# LWOC_2_0.net
KiCad netlist of a schematic drawn in EAGLE
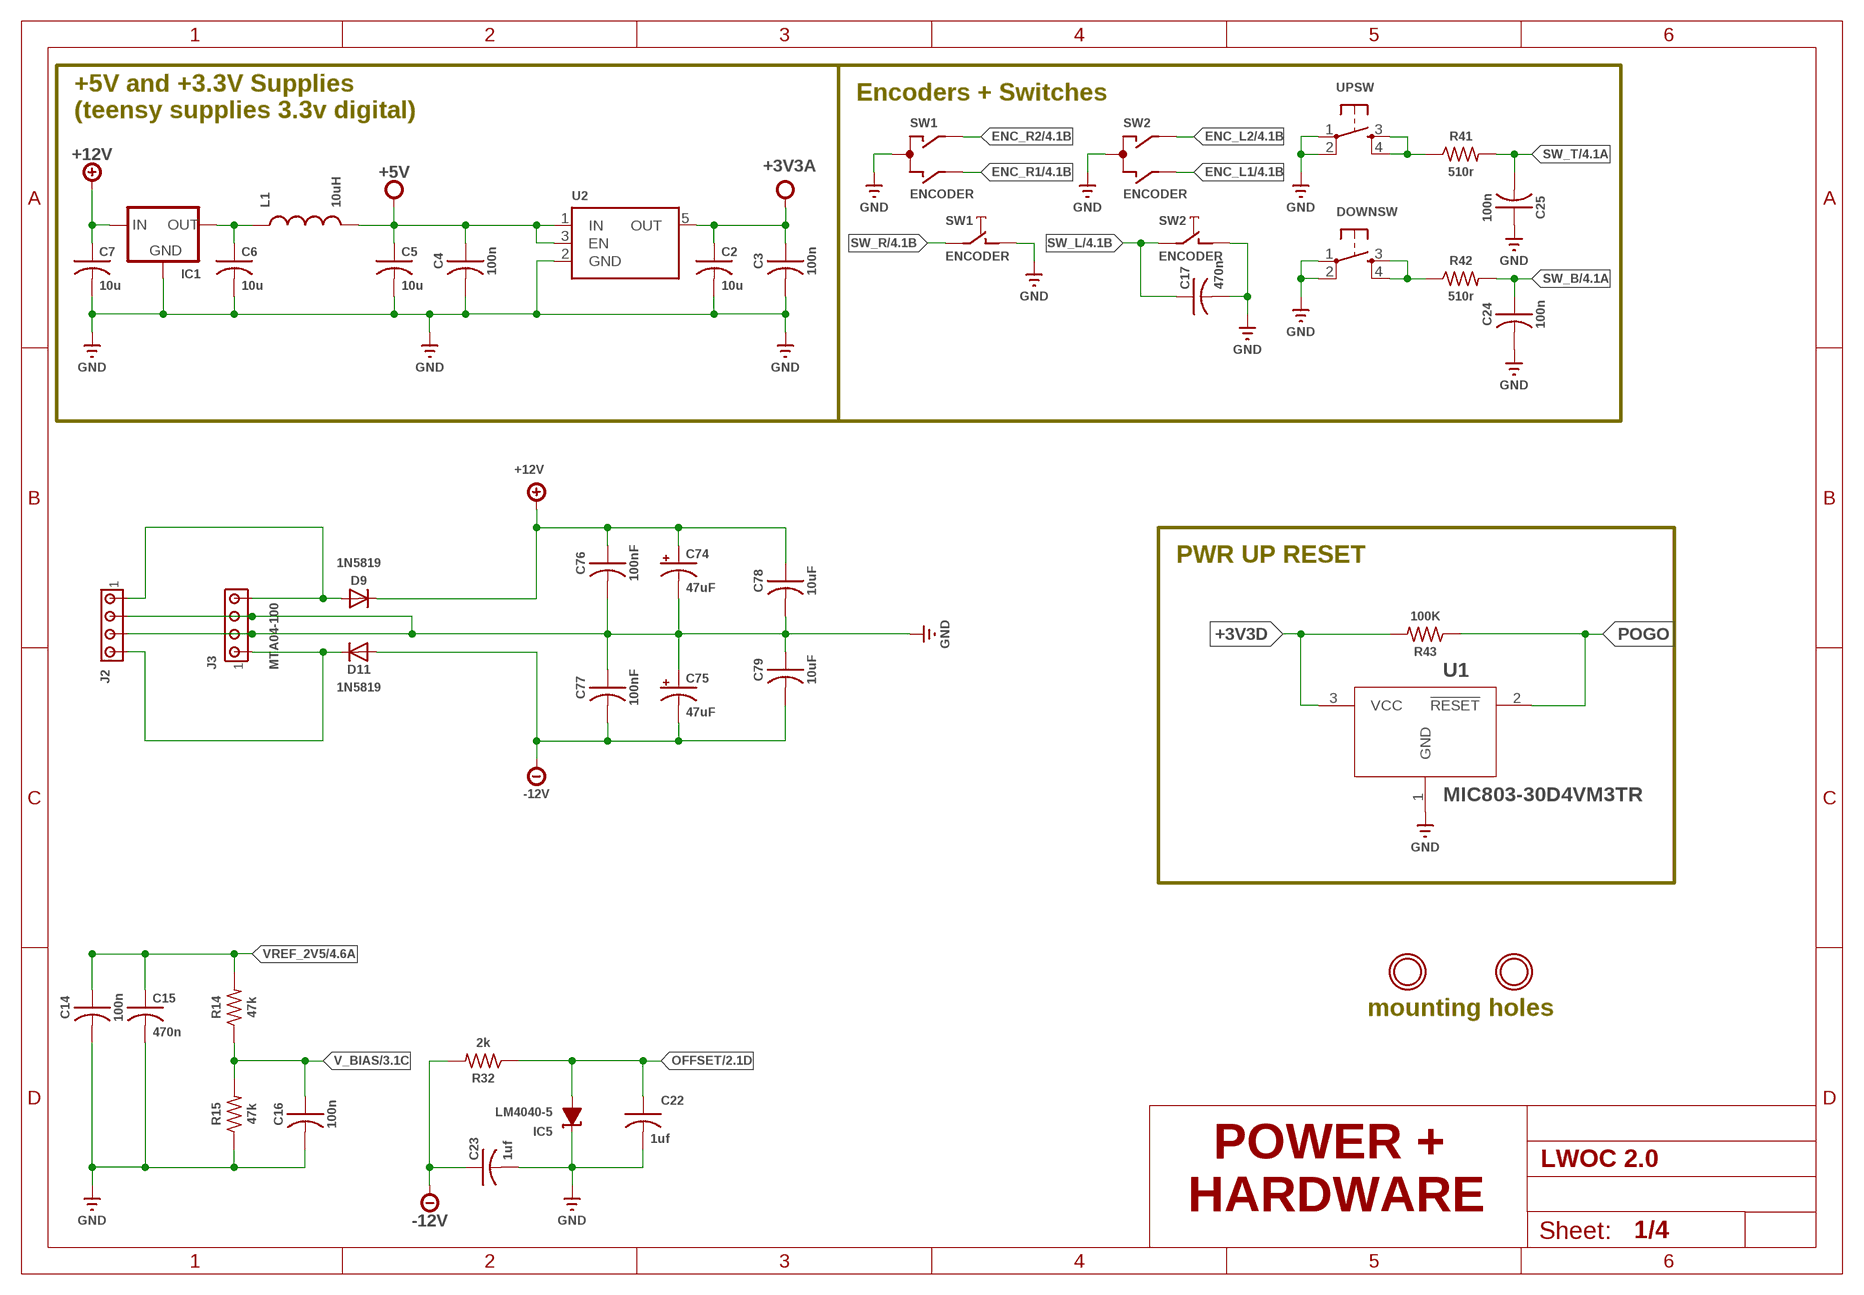
[diagram p0: schematic, sheet 1]
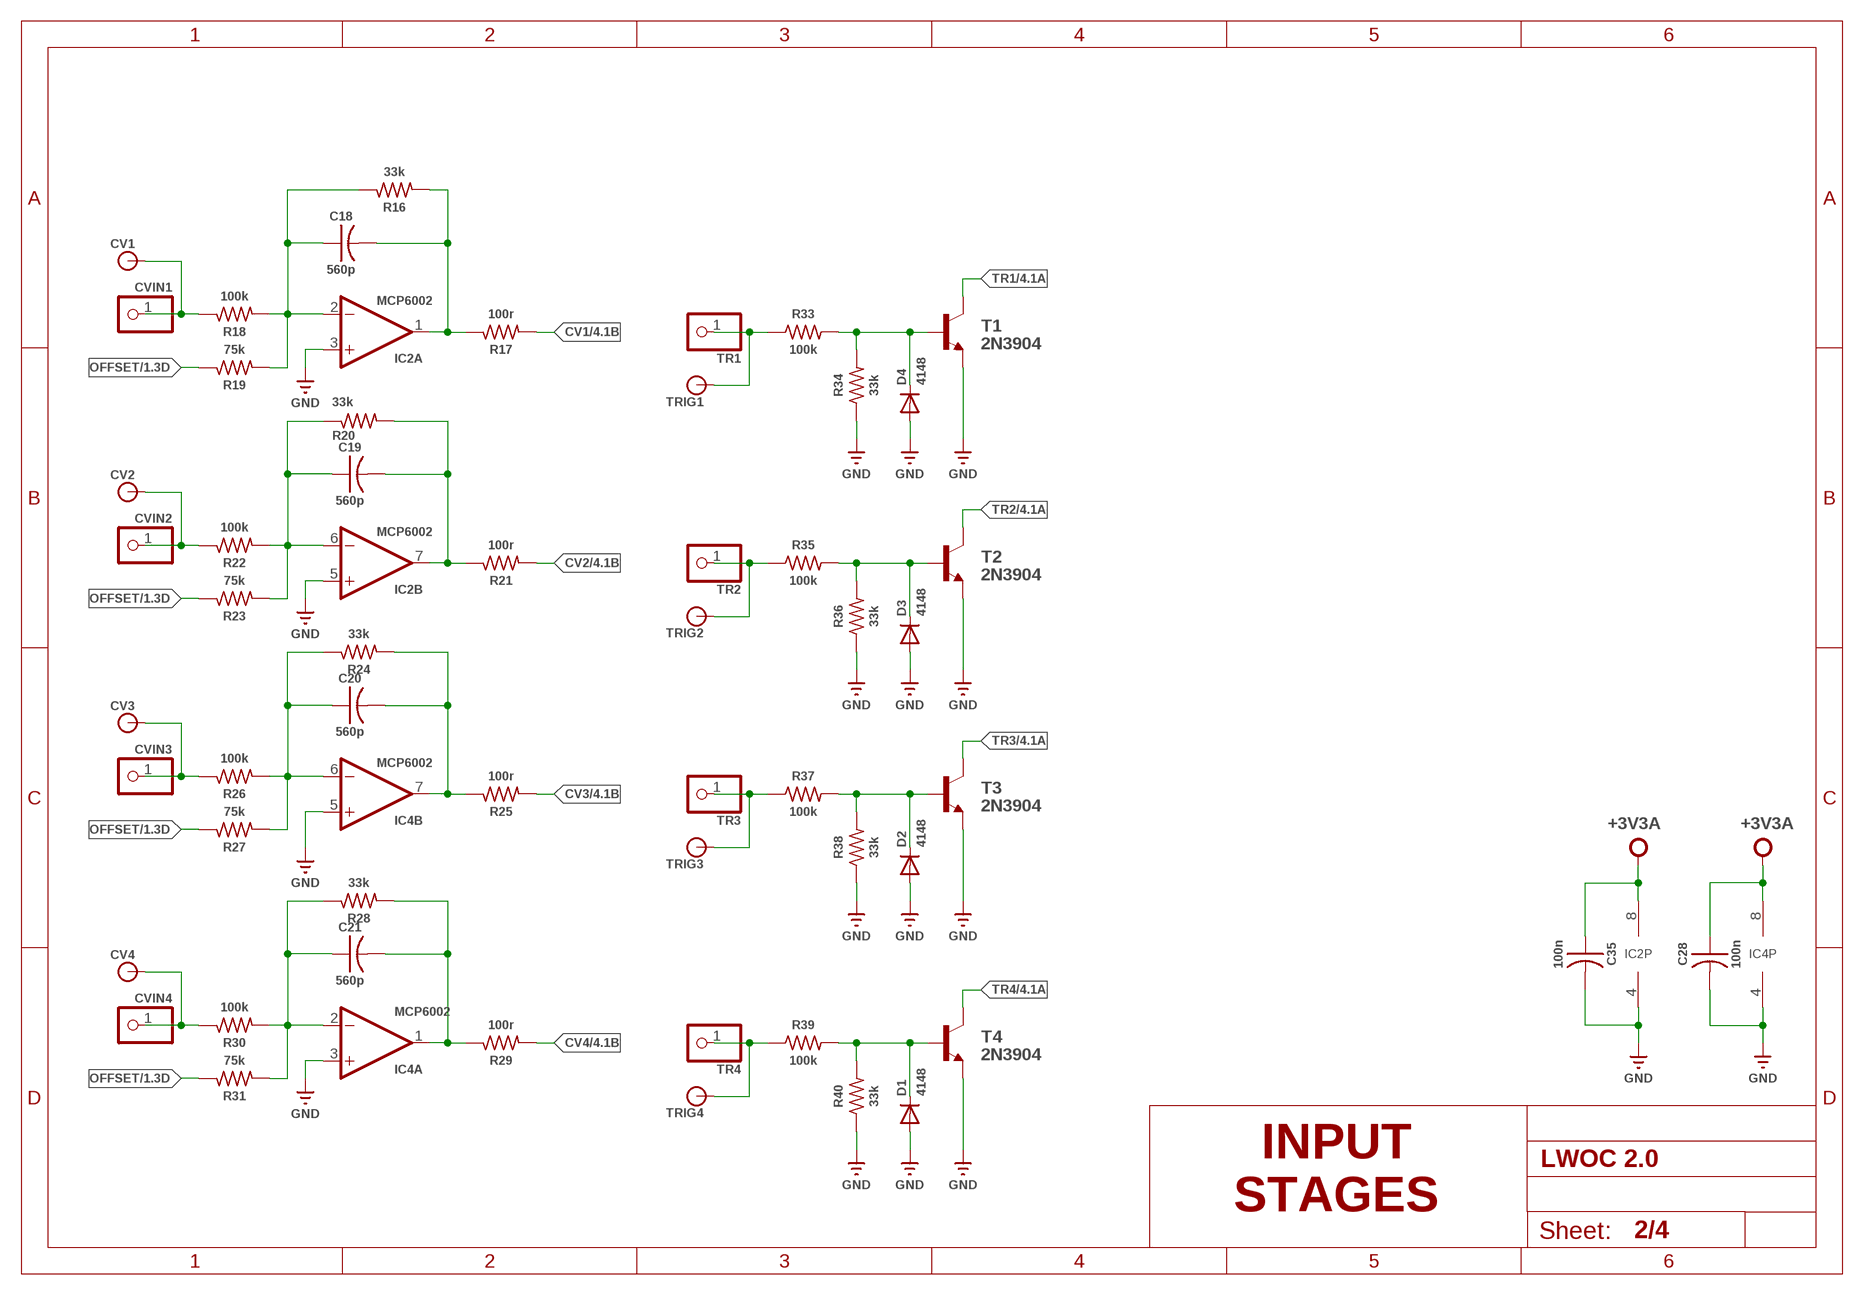
[diagram p1: schematic, sheet 2]
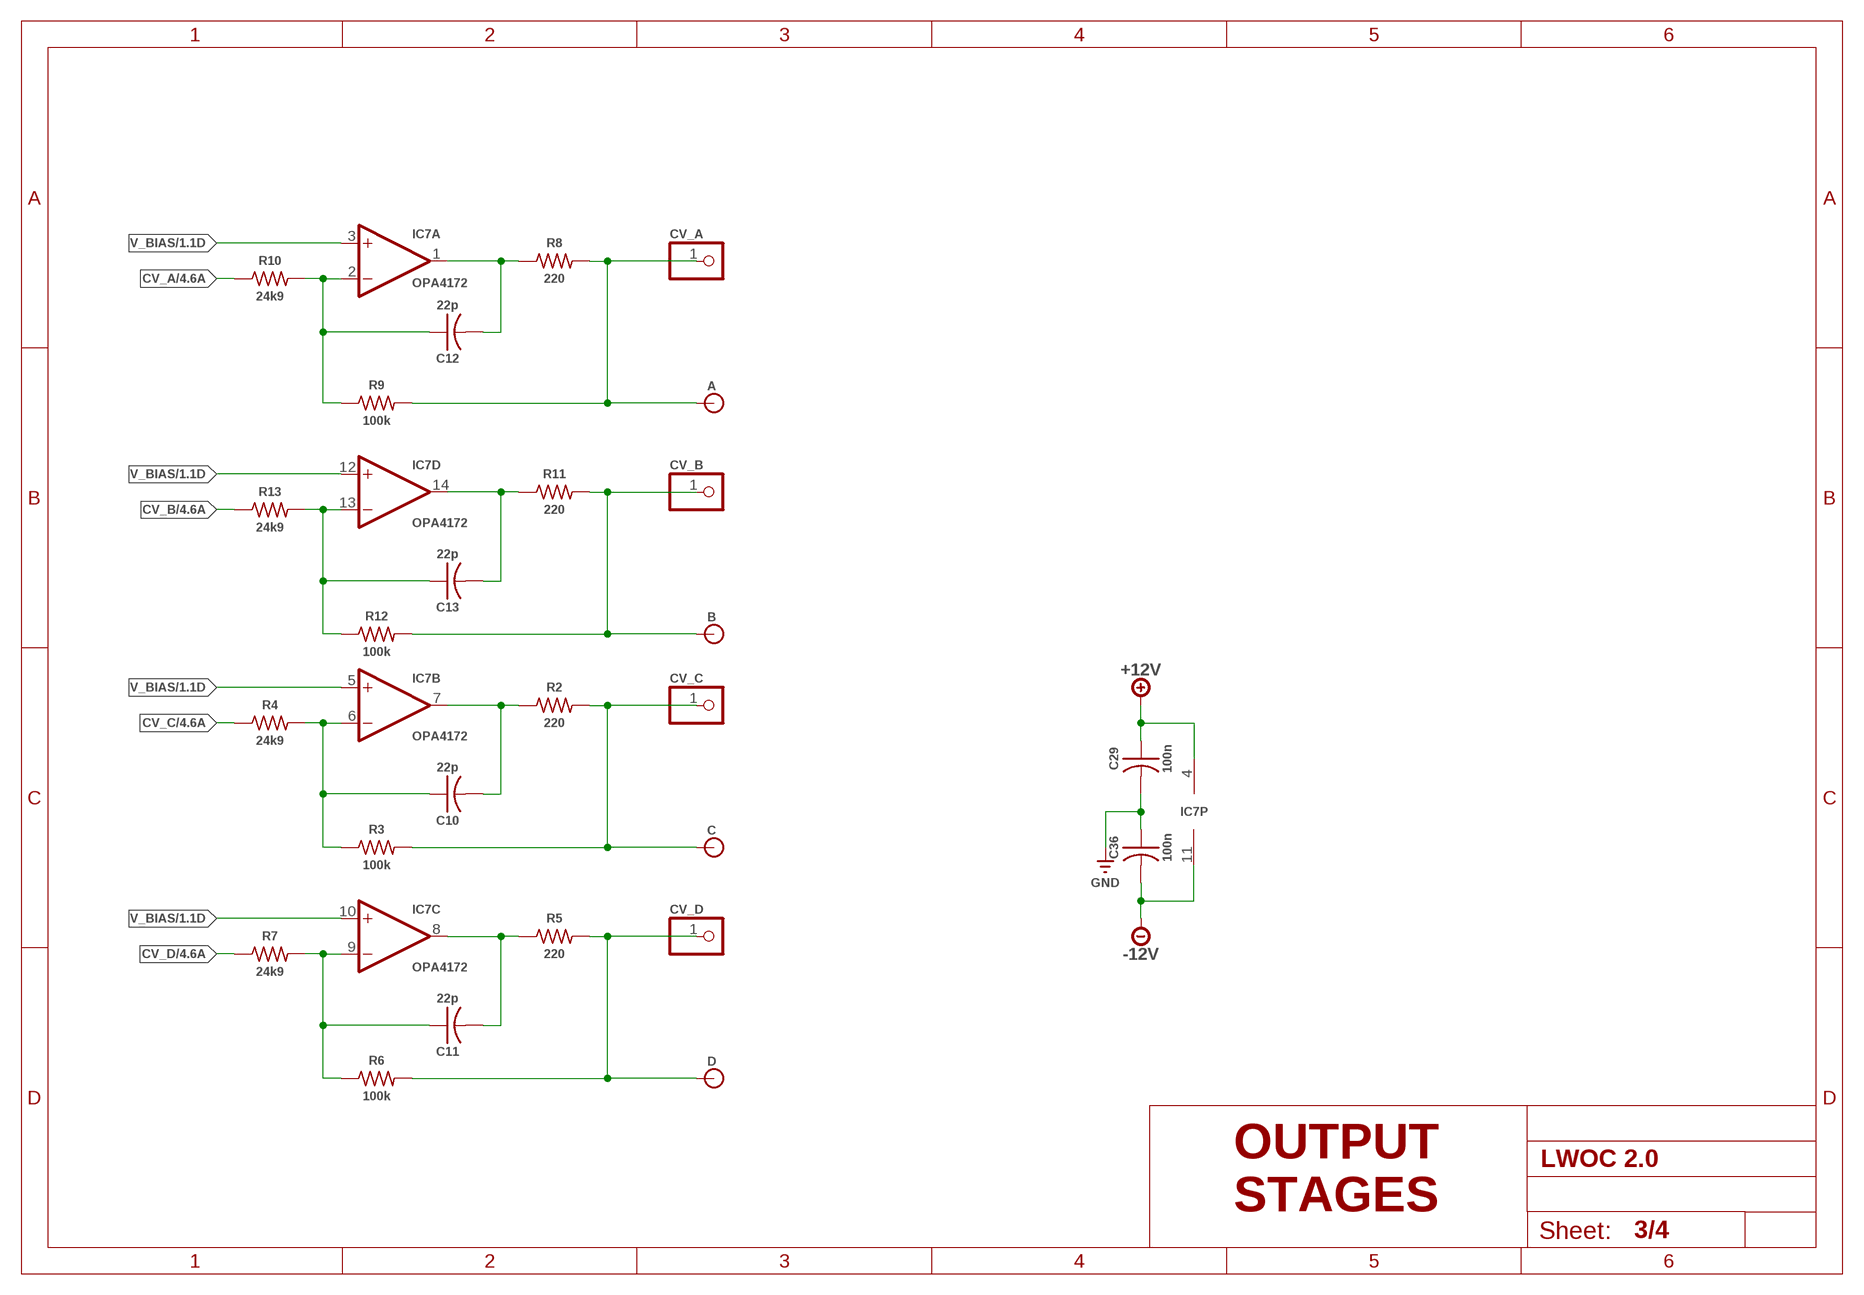
[diagram p2: schematic, sheet 3]
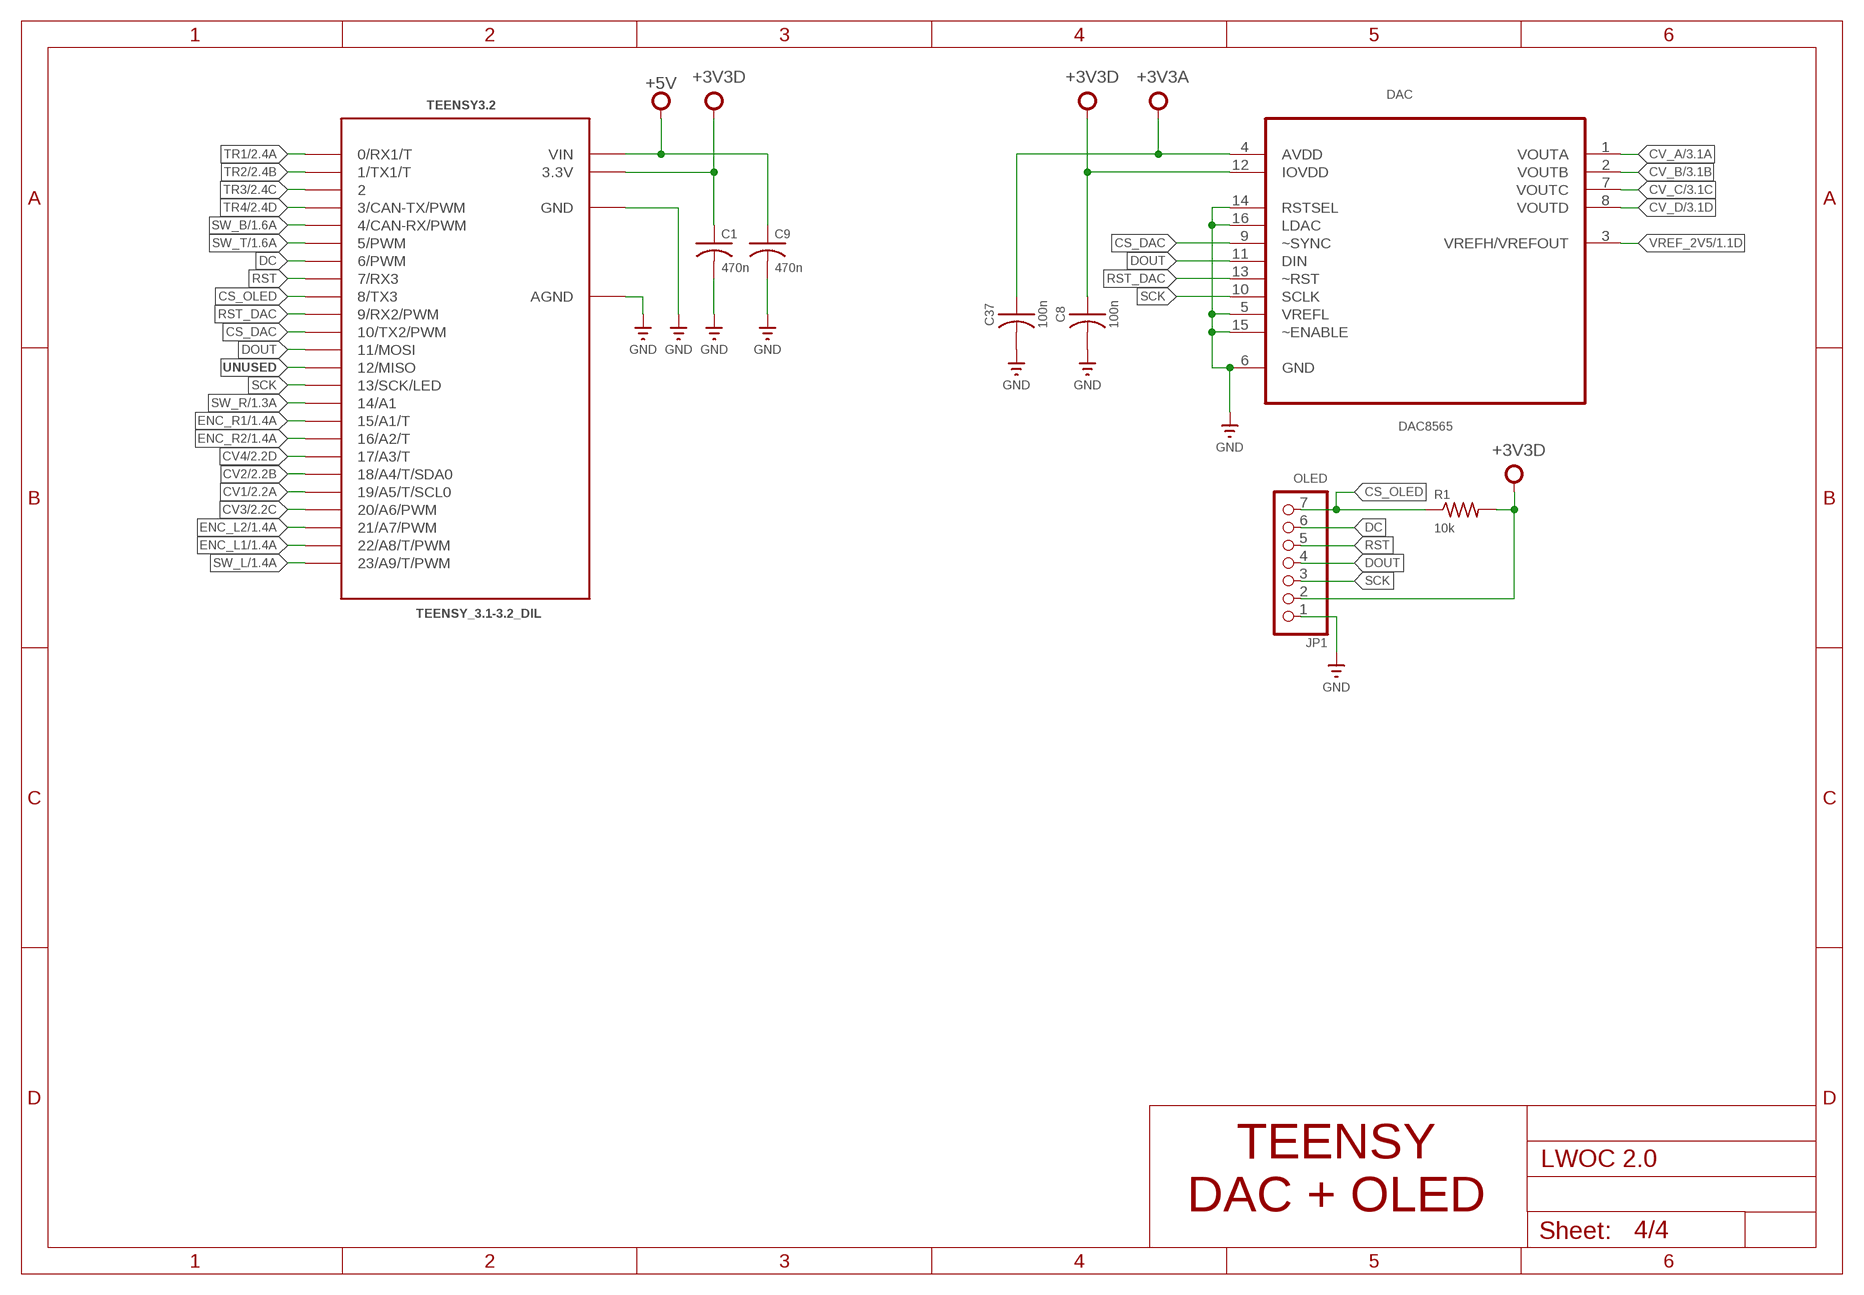
[diagram p3: schematic, sheet 4]

(export (version "E")
  (design (tool "Eeschema 10.0.6"))
  (components
    (comp (ref "C2")
      (value "10u")
      (footprint "eagle-import:C1206K")
      (libsource (lib "eagle-import") (part "C-USC1206K"))
    )
    (comp (ref "C3")
      (value "100n")
      (footprint "eagle-import:RCL_C0603K")
      (libsource (lib "eagle-import") (part "RCL_C-USC0603K"))
    )
    (comp (ref "C4")
      (value "100n")
      (footprint "eagle-import:RCL_C0603K")
      (libsource (lib "eagle-import") (part "RCL_C-USC0603K"))
    )
    (comp (ref "C5")
      (value "10u")
      (footprint "eagle-import:C1206K")
      (libsource (lib "eagle-import") (part "C-USC1206K"))
    )
    (comp (ref "C6")
      (value "10u")
      (footprint "eagle-import:C1206K")
      (libsource (lib "eagle-import") (part "C-USC1206K"))
    )
    (comp (ref "C7")
      (value "10u")
      (footprint "eagle-import:C1206K")
      (libsource (lib "eagle-import") (part "C-USC1206K"))
    )
    (comp (ref "C14")
      (value "100n")
      (footprint "eagle-import:RCL_C0603K")
      (libsource (lib "eagle-import") (part "RCL_C-USC0603K"))
    )
    (comp (ref "C15")
      (value "470n")
      (footprint "eagle-import:RCL_C0603K")
      (libsource (lib "eagle-import") (part "RCL_C-USC0603K"))
    )
    (comp (ref "C16")
      (value "100n")
      (footprint "eagle-import:RCL_C0603K")
      (libsource (lib "eagle-import") (part "RCL_C-USC0603K"))
    )
    (comp (ref "C17")
      (value "470n")
      (footprint "eagle-import:C0805K")
      (libsource (lib "eagle-import") (part "C-USC0805K"))
    )
    (comp (ref "C22")
      (value "1uf")
      (footprint "eagle-import:C0805K")
      (libsource (lib "eagle-import") (part "C-USC0805K"))
    )
    (comp (ref "C23")
      (value "1uf")
      (footprint "eagle-import:C0805K")
      (libsource (lib "eagle-import") (part "C-USC0805K"))
    )
    (comp (ref "C24")
      (value "100n")
      (footprint "eagle-import:RCL_C0603K")
      (libsource (lib "eagle-import") (part "RCL_C-USC0603K"))
    )
    (comp (ref "C25")
      (value "100n")
      (footprint "eagle-import:RCL_C0603K")
      (libsource (lib "eagle-import") (part "RCL_C-USC0603K"))
    )
    (comp (ref "C74")
      (value "47uF")
      (footprint "eagle-import:RCL_E2,5-6")
      (libsource (lib "eagle-import") (part "RCL_CPOL-USE2.5-6"))
    )
    (comp (ref "C75")
      (value "47uF")
      (footprint "eagle-import:RCL_E2,5-6")
      (libsource (lib "eagle-import") (part "RCL_CPOL-USE2.5-6"))
    )
    (comp (ref "C76")
      (value "100nF")
      (footprint "eagle-import:RCL_C0603K")
      (libsource (lib "eagle-import") (part "ripples_v40_RCL_C-USC0603K"))
    )
    (comp (ref "C77")
      (value "100nF")
      (footprint "eagle-import:RCL_C0603K")
      (libsource (lib "eagle-import") (part "ripples_v40_RCL_C-USC0603K"))
    )
    (comp (ref "C78")
      (value "10uF")
      (footprint "eagle-import:RCL_C1210")
      (libsource (lib "eagle-import") (part "RCL_C-USC1210"))
    )
    (comp (ref "C79")
      (value "10uF")
      (footprint "eagle-import:RCL_C1210")
      (libsource (lib "eagle-import") (part "RCL_C-USC1210"))
    )
    (comp (ref "D9")
      (value "1N5819")
      (footprint "eagle-import:DIODE_SOD323-W")
      (libsource (lib "eagle-import") (part "ripples_v40_DIODE_DIODE-SOD323-W"))
    )
    (comp (ref "D11")
      (value "1N5819")
      (footprint "eagle-import:DIODE_SOD323-W")
      (libsource (lib "eagle-import") (part "ripples_v40_DIODE_DIODE-SOD323-W"))
    )
    (comp (ref "DOWNSW")
      (value "SPARKFUN_TAC_SWITCHPTH")
      (footprint "eagle-import:SPARKFUN_TACTILE-PTH")
      (libsource (lib "eagle-import") (part "SPARKFUN_TAC_SWITCHPTH"))
    )
    (comp (ref "IC1")
      (value "LM1117TO252")
      (footprint "eagle-import:TO252")
      (libsource (lib "eagle-import") (part "LM1117TO252"))
    )
    (comp (ref "IC5")
      (value "LM4040-5")
      (footprint "eagle-import:DBZ_R-PDSO-G3")
      (libsource (lib "eagle-import") (part "LM4041DBZA12"))
    )
    (comp (ref "J2")
      (value "MTA04-156")
      (footprint "eagle-import:1X4MTA")
      (libsource (lib "eagle-import") (part "MTA04-156"))
    )
    (comp (ref "J3")
      (value "MTA04-100")
      (footprint "eagle-import:1X04MTA")
      (libsource (lib "eagle-import") (part "MTA04-100"))
    )
    (comp (ref "L1")
      (value "10uH")
      (footprint "eagle-import:1210")
      (libsource (lib "eagle-import") (part "INDUCTOR1210"))
    )
    (comp (ref "R14")
      (value "47k")
      (footprint "eagle-import:RCL_R0603")
      (libsource (lib "eagle-import") (part "RCL_R-US_R0603"))
    )
    (comp (ref "R15")
      (value "47k")
      (footprint "eagle-import:RCL_R0603")
      (libsource (lib "eagle-import") (part "RCL_R-US_R0603"))
    )
    (comp (ref "R32")
      (value "2k")
      (footprint "eagle-import:RCL_R0603")
      (libsource (lib "eagle-import") (part "RCL_R-US_R0603"))
    )
    (comp (ref "R41")
      (value "510r")
      (footprint "eagle-import:RCL_R0603")
      (libsource (lib "eagle-import") (part "RCL_R-US_R0603"))
    )
    (comp (ref "R42")
      (value "510r")
      (footprint "eagle-import:RCL_R0603")
      (libsource (lib "eagle-import") (part "RCL_R-US_R0603"))
    )
    (comp (ref "R43")
      (value "100K")
      (footprint "eagle-import:RCL_R0603")
      (libsource (lib "eagle-import") (part "RCL_R-US_R0603"))
    )
    (comp (ref "SW1")
      (value "ENCODER")
      (footprint "eagle-import:OG-ENCODER_ALPS_EC12E_SW")
      (libsource (lib "eagle-import") (part "OG-ENCODER_EC12E_SW"))
    )
    (comp (ref "SW2")
      (value "ENCODER")
      (footprint "eagle-import:OG-ENCODER_ALPS_EC12E_SW")
      (libsource (lib "eagle-import") (part "OG-ENCODER_EC12E_SW"))
    )
    (comp (ref "U$23")
      (value "MOUNTINGHOLE2.5")
      (footprint "eagle-import:MOUNTINGHOLE_2.5_PLATED")
      (libsource (lib "eagle-import") (part "MOUNTINGHOLE2.5"))
    )
    (comp (ref "U$26")
      (value "MOUNTINGHOLE2.5")
      (footprint "eagle-import:MOUNTINGHOLE_2.5_PLATED")
      (libsource (lib "eagle-import") (part "MOUNTINGHOLE2.5"))
    )
    (comp (ref "U1")
      (value "MIC803-30D4VM3TR")
      (footprint "eagle-import:SOT95P232X110-3N")
      (libsource (lib "eagle-import") (part "MIC803-30D4VM3TR"))
    )
    (comp (ref "U2")
      (value "ADP121")
      (footprint "eagle-import:SOT23-5")
      (libsource (lib "eagle-import") (part "ADP121"))
    )
    (comp (ref "UPSW")
      (value "SPARKFUN_TAC_SWITCHPTH")
      (footprint "eagle-import:SPARKFUN_TACTILE-PTH")
      (libsource (lib "eagle-import") (part "SPARKFUN_TAC_SWITCHPTH"))
    )
    (comp (ref "A")
      (value "BANANA_CONN")
      (footprint "eagle-import:BANANA_CONN")
      (libsource (lib "eagle-import") (part "BANANA_CONN"))
    )
    (comp (ref "B")
      (value "BANANA_CONN")
      (footprint "eagle-import:BANANA_CONN")
      (libsource (lib "eagle-import") (part "BANANA_CONN"))
    )
    (comp (ref "C")
      (value "BANANA_CONN")
      (footprint "eagle-import:BANANA_CONN")
      (libsource (lib "eagle-import") (part "BANANA_CONN"))
    )
    (comp (ref "C10")
      (value "22p")
      (footprint "eagle-import:RCL_C0603K")
      (libsource (lib "eagle-import") (part "RCL_C-USC0603K"))
    )
    (comp (ref "C11")
      (value "22p")
      (footprint "eagle-import:RCL_C0603K")
      (libsource (lib "eagle-import") (part "RCL_C-USC0603K"))
    )
    (comp (ref "C12")
      (value "22p")
      (footprint "eagle-import:RCL_C0603K")
      (libsource (lib "eagle-import") (part "RCL_C-USC0603K"))
    )
    (comp (ref "C13")
      (value "22p")
      (footprint "eagle-import:RCL_C0603K")
      (libsource (lib "eagle-import") (part "RCL_C-USC0603K"))
    )
    (comp (ref "C29")
      (value "100n")
      (footprint "eagle-import:RCL_C0603K")
      (libsource (lib "eagle-import") (part "RCL_C-USC0603K"))
    )
    (comp (ref "C36")
      (value "100n")
      (footprint "eagle-import:RCL_C0603K")
      (libsource (lib "eagle-import") (part "RCL_C-USC0603K"))
    )
    (comp (ref "CV_A")
      (value "PINHD-1X1")
      (footprint "eagle-import:1X01")
      (libsource (lib "eagle-import") (part "PINHD-1X1"))
    )
    (comp (ref "CV_B")
      (value "PINHD-1X1")
      (footprint "eagle-import:1X01")
      (libsource (lib "eagle-import") (part "PINHD-1X1"))
    )
    (comp (ref "CV_C")
      (value "PINHD-1X1")
      (footprint "eagle-import:1X01")
      (libsource (lib "eagle-import") (part "PINHD-1X1"))
    )
    (comp (ref "CV_D")
      (value "PINHD-1X1")
      (footprint "eagle-import:1X01")
      (libsource (lib "eagle-import") (part "PINHD-1X1"))
    )
    (comp (ref "D")
      (value "BANANA_CONN")
      (footprint "eagle-import:BANANA_CONN")
      (libsource (lib "eagle-import") (part "BANANA_CONN"))
    )
    (comp (ref "IC7")
      (value "OPA4172")
      (footprint "eagle-import:GM-ICS_SO14")
      (libsource (lib "eagle-import") (part "GM-ICS_TL074D"))
    )
    (comp (ref "R2")
      (value "220")
      (footprint "eagle-import:RCL_R0603")
      (libsource (lib "eagle-import") (part "RCL_R-US_R0603"))
    )
    (comp (ref "R3")
      (value "100k")
      (footprint "eagle-import:RCL_R0603")
      (libsource (lib "eagle-import") (part "RCL_R-US_R0603"))
    )
    (comp (ref "R4")
      (value "24k9")
      (footprint "eagle-import:RCL_R0603")
      (libsource (lib "eagle-import") (part "RCL_R-US_R0603"))
    )
    (comp (ref "R5")
      (value "220")
      (footprint "eagle-import:RCL_R0603")
      (libsource (lib "eagle-import") (part "RCL_R-US_R0603"))
    )
    (comp (ref "R6")
      (value "100k")
      (footprint "eagle-import:RCL_R0603")
      (libsource (lib "eagle-import") (part "RCL_R-US_R0603"))
    )
    (comp (ref "R7")
      (value "24k9")
      (footprint "eagle-import:RCL_R0603")
      (libsource (lib "eagle-import") (part "RCL_R-US_R0603"))
    )
    (comp (ref "R8")
      (value "220")
      (footprint "eagle-import:RCL_R0603")
      (libsource (lib "eagle-import") (part "RCL_R-US_R0603"))
    )
    (comp (ref "R9")
      (value "100k")
      (footprint "eagle-import:RCL_R0603")
      (libsource (lib "eagle-import") (part "RCL_R-US_R0603"))
    )
    (comp (ref "R10")
      (value "24k9")
      (footprint "eagle-import:RCL_R0603")
      (libsource (lib "eagle-import") (part "RCL_R-US_R0603"))
    )
    (comp (ref "R11")
      (value "220")
      (footprint "eagle-import:RCL_R0603")
      (libsource (lib "eagle-import") (part "RCL_R-US_R0603"))
    )
    (comp (ref "R12")
      (value "100k")
      (footprint "eagle-import:RCL_R0603")
      (libsource (lib "eagle-import") (part "RCL_R-US_R0603"))
    )
    (comp (ref "R13")
      (value "24k9")
      (footprint "eagle-import:RCL_R0603")
      (libsource (lib "eagle-import") (part "RCL_R-US_R0603"))
    )
    (comp (ref "C18")
      (value "560p")
      (footprint "eagle-import:RCL_C0603K")
      (libsource (lib "eagle-import") (part "RCL_C-USC0603K"))
    )
    (comp (ref "C19")
      (value "560p")
      (footprint "eagle-import:RCL_C0603K")
      (libsource (lib "eagle-import") (part "RCL_C-USC0603K"))
    )
    (comp (ref "C20")
      (value "560p")
      (footprint "eagle-import:RCL_C0603K")
      (libsource (lib "eagle-import") (part "RCL_C-USC0603K"))
    )
    (comp (ref "C21")
      (value "560p")
      (footprint "eagle-import:RCL_C0603K")
      (libsource (lib "eagle-import") (part "RCL_C-USC0603K"))
    )
    (comp (ref "C28")
      (value "100n")
      (footprint "eagle-import:RCL_C0603K")
      (libsource (lib "eagle-import") (part "RCL_C-USC0603K"))
    )
    (comp (ref "C35")
      (value "100n")
      (footprint "eagle-import:RCL_C0603K")
      (libsource (lib "eagle-import") (part "RCL_C-USC0603K"))
    )
    (comp (ref "CV1")
      (value "BANANA_CONN")
      (footprint "eagle-import:BANANA_CONN")
      (libsource (lib "eagle-import") (part "BANANA_CONN"))
    )
    (comp (ref "CV2")
      (value "BANANA_CONN")
      (footprint "eagle-import:BANANA_CONN")
      (libsource (lib "eagle-import") (part "BANANA_CONN"))
    )
    (comp (ref "CV3")
      (value "BANANA_CONN")
      (footprint "eagle-import:BANANA_CONN")
      (libsource (lib "eagle-import") (part "BANANA_CONN"))
    )
    (comp (ref "CV4")
      (value "BANANA_CONN")
      (footprint "eagle-import:BANANA_CONN")
      (libsource (lib "eagle-import") (part "BANANA_CONN"))
    )
    (comp (ref "CVIN1")
      (value "PINHD-1X1")
      (footprint "eagle-import:1X01")
      (libsource (lib "eagle-import") (part "PINHD-1X1"))
    )
    (comp (ref "CVIN2")
      (value "PINHD-1X1")
      (footprint "eagle-import:1X01")
      (libsource (lib "eagle-import") (part "PINHD-1X1"))
    )
    (comp (ref "CVIN3")
      (value "PINHD-1X1")
      (footprint "eagle-import:1X01")
      (libsource (lib "eagle-import") (part "PINHD-1X1"))
    )
    (comp (ref "CVIN4")
      (value "PINHD-1X1")
      (footprint "eagle-import:1X01")
      (libsource (lib "eagle-import") (part "PINHD-1X1"))
    )
    (comp (ref "D1")
      (value "4148")
      (footprint "eagle-import:DIODE_SOD323-W")
      (libsource (lib "eagle-import") (part "DIODE_DIODE-SOD323-W"))
    )
    (comp (ref "D2")
      (value "4148")
      (footprint "eagle-import:DIODE_SOD323-W")
      (libsource (lib "eagle-import") (part "DIODE_DIODE-SOD323-W"))
    )
    (comp (ref "D3")
      (value "4148")
      (footprint "eagle-import:DIODE_SOD323-W")
      (libsource (lib "eagle-import") (part "DIODE_DIODE-SOD323-W"))
    )
    (comp (ref "D4")
      (value "4148")
      (footprint "eagle-import:DIODE_SOD323-W")
      (libsource (lib "eagle-import") (part "DIODE_DIODE-SOD323-W"))
    )
    (comp (ref "IC2")
      (value "MCP6002")
      (footprint "eagle-import:GM-ICS_SO08")
      (libsource (lib "eagle-import") (part "GM-ICS_TL072D"))
    )
    (comp (ref "IC4")
      (value "MCP6002")
      (footprint "eagle-import:GM-ICS_SO08")
      (libsource (lib "eagle-import") (part "GM-ICS_TL072D"))
    )
    (comp (ref "R16")
      (value "33k")
      (footprint "eagle-import:RCL_R0603")
      (libsource (lib "eagle-import") (part "RCL_R-US_R0603"))
    )
    (comp (ref "R17")
      (value "100r")
      (footprint "eagle-import:RCL_R0603")
      (libsource (lib "eagle-import") (part "RCL_R-US_R0603"))
    )
    (comp (ref "R18")
      (value "100k")
      (footprint "eagle-import:RCL_R0603")
      (libsource (lib "eagle-import") (part "RCL_R-US_R0603"))
    )
    (comp (ref "R19")
      (value "75k")
      (footprint "eagle-import:RCL_R0603")
      (libsource (lib "eagle-import") (part "RCL_R-US_R0603"))
    )
    (comp (ref "R20")
      (value "33k")
      (footprint "eagle-import:RCL_R0603")
      (libsource (lib "eagle-import") (part "RCL_R-US_R0603"))
    )
    (comp (ref "R21")
      (value "100r")
      (footprint "eagle-import:RCL_R0603")
      (libsource (lib "eagle-import") (part "RCL_R-US_R0603"))
    )
    (comp (ref "R22")
      (value "100k")
      (footprint "eagle-import:RCL_R0603")
      (libsource (lib "eagle-import") (part "RCL_R-US_R0603"))
    )
    (comp (ref "R23")
      (value "75k")
      (footprint "eagle-import:RCL_R0603")
      (libsource (lib "eagle-import") (part "RCL_R-US_R0603"))
    )
    (comp (ref "R24")
      (value "33k")
      (footprint "eagle-import:RCL_R0603")
      (libsource (lib "eagle-import") (part "RCL_R-US_R0603"))
    )
    (comp (ref "R25")
      (value "100r")
      (footprint "eagle-import:RCL_R0603")
      (libsource (lib "eagle-import") (part "RCL_R-US_R0603"))
    )
    (comp (ref "R26")
      (value "100k")
      (footprint "eagle-import:RCL_R0603")
      (libsource (lib "eagle-import") (part "RCL_R-US_R0603"))
    )
    (comp (ref "R27")
      (value "75k")
      (footprint "eagle-import:RCL_R0603")
      (libsource (lib "eagle-import") (part "RCL_R-US_R0603"))
    )
    (comp (ref "R28")
      (value "33k")
      (footprint "eagle-import:RCL_R0603")
      (libsource (lib "eagle-import") (part "RCL_R-US_R0603"))
    )
    (comp (ref "R29")
      (value "100r")
      (footprint "eagle-import:RCL_R0603")
      (libsource (lib "eagle-import") (part "RCL_R-US_R0603"))
    )
    (comp (ref "R30")
      (value "100k")
      (footprint "eagle-import:RCL_R0603")
      (libsource (lib "eagle-import") (part "RCL_R-US_R0603"))
    )
    (comp (ref "R31")
      (value "75k")
      (footprint "eagle-import:RCL_R0603")
      (libsource (lib "eagle-import") (part "RCL_R-US_R0603"))
    )
    (comp (ref "R33")
      (value "100k")
      (footprint "eagle-import:RCL_R0603")
      (libsource (lib "eagle-import") (part "RCL_R-US_R0603"))
    )
    (comp (ref "R34")
      (value "33k")
      (footprint "eagle-import:RCL_R0603")
      (libsource (lib "eagle-import") (part "RCL_R-US_R0603"))
    )
    (comp (ref "R35")
      (value "100k")
      (footprint "eagle-import:RCL_R0603")
      (libsource (lib "eagle-import") (part "RCL_R-US_R0603"))
    )
    (comp (ref "R36")
      (value "33k")
      (footprint "eagle-import:RCL_R0603")
      (libsource (lib "eagle-import") (part "RCL_R-US_R0603"))
    )
    (comp (ref "R37")
      (value "100k")
      (footprint "eagle-import:RCL_R0603")
      (libsource (lib "eagle-import") (part "RCL_R-US_R0603"))
    )
    (comp (ref "R38")
      (value "33k")
      (footprint "eagle-import:RCL_R0603")
      (libsource (lib "eagle-import") (part "RCL_R-US_R0603"))
    )
    (comp (ref "R39")
      (value "100k")
      (footprint "eagle-import:RCL_R0603")
      (libsource (lib "eagle-import") (part "RCL_R-US_R0603"))
    )
    (comp (ref "R40")
      (value "33k")
      (footprint "eagle-import:RCL_R0603")
      (libsource (lib "eagle-import") (part "RCL_R-US_R0603"))
    )
    (comp (ref "T1")
      (value "2N3904")
      (footprint "eagle-import:SOT23-BEC")
      (libsource (lib "eagle-import") (part "-NPN-SOT23-BECMMBT3904LT1"))
    )
    (comp (ref "T2")
      (value "2N3904")
      (footprint "eagle-import:SOT23-BEC")
      (libsource (lib "eagle-import") (part "-NPN-SOT23-BECMMBT3904LT1"))
    )
    (comp (ref "T3")
      (value "2N3904")
      (footprint "eagle-import:SOT23-BEC")
      (libsource (lib "eagle-import") (part "-NPN-SOT23-BECMMBT3904LT1"))
    )
    (comp (ref "T4")
      (value "2N3904")
      (footprint "eagle-import:SOT23-BEC")
      (libsource (lib "eagle-import") (part "-NPN-SOT23-BECMMBT3904LT1"))
    )
    (comp (ref "TR1")
      (value "PINHD-1X1")
      (footprint "eagle-import:1X01")
      (libsource (lib "eagle-import") (part "PINHD-1X1"))
    )
    (comp (ref "TR2")
      (value "PINHD-1X1")
      (footprint "eagle-import:1X01")
      (libsource (lib "eagle-import") (part "PINHD-1X1"))
    )
    (comp (ref "TR3")
      (value "PINHD-1X1")
      (footprint "eagle-import:1X01")
      (libsource (lib "eagle-import") (part "PINHD-1X1"))
    )
    (comp (ref "TR4")
      (value "PINHD-1X1")
      (footprint "eagle-import:1X01")
      (libsource (lib "eagle-import") (part "PINHD-1X1"))
    )
    (comp (ref "TRIG1")
      (value "BANANA_CONN")
      (footprint "eagle-import:BANANA_CONN")
      (libsource (lib "eagle-import") (part "BANANA_CONN"))
    )
    (comp (ref "TRIG2")
      (value "BANANA_CONN")
      (footprint "eagle-import:BANANA_CONN")
      (libsource (lib "eagle-import") (part "BANANA_CONN"))
    )
    (comp (ref "TRIG3")
      (value "BANANA_CONN")
      (footprint "eagle-import:BANANA_CONN")
      (libsource (lib "eagle-import") (part "BANANA_CONN"))
    )
    (comp (ref "TRIG4")
      (value "BANANA_CONN")
      (footprint "eagle-import:BANANA_CONN")
      (libsource (lib "eagle-import") (part "BANANA_CONN"))
    )
    (comp (ref "C1")
      (value "470n")
      (footprint "eagle-import:C0805K")
      (libsource (lib "eagle-import") (part "C-USC0805K"))
    )
    (comp (ref "C8")
      (value "100n")
      (footprint "eagle-import:RCL_C0603K")
      (libsource (lib "eagle-import") (part "RCL_C-USC0603K"))
    )
    (comp (ref "C9")
      (value "470n")
      (footprint "eagle-import:C0805K")
      (libsource (lib "eagle-import") (part "C-USC0805K"))
    )
    (comp (ref "C37")
      (value "100n")
      (footprint "eagle-import:RCL_C0603K")
      (libsource (lib "eagle-import") (part "RCL_C-USC0603K"))
    )
    (comp (ref "DAC")
      (value "DAC8565")
      (footprint "eagle-import:SOP65P640X120-16N")
      (fields (field (name "MF") "Texas Instruments") (field (name "MP") "DAC8565IAPW"))
      (libsource (lib "eagle-import") (part "DAC8565IAPW"))
    )
    (comp (ref "JP1")
      (value "OLED")
      (footprint "eagle-import:1X07")
      (libsource (lib "eagle-import") (part "PINHD-1X7"))
    )
    (comp (ref "R1")
      (value "10k")
      (footprint "eagle-import:M0805")
      (libsource (lib "eagle-import") (part "R-US_M0805"))
    )
    (comp (ref "TEENSY3.2")
      (value "TEENSY_3.1-3.2_DIL")
      (footprint "eagle-import:TEENSY_3.0-3.2&LC_DIL")
      (libsource (lib "eagle-import") (part "TEENSY_3.1-3.2_DIL"))
    )
  )
  (nets
    (net (code "1") (name "+3V3A") (class "Default")
      (node (ref "C2") (pin "1") (pinfunction "1_1") (pintype "passive"))
      (node (ref "C28") (pin "1") (pinfunction "1_1") (pintype "passive"))
      (node (ref "C3") (pin "1") (pinfunction "1_1") (pintype "passive"))
      (node (ref "C35") (pin "1") (pinfunction "1_1") (pintype "passive"))
      (node (ref "C37") (pin "1") (pinfunction "1_1") (pintype "passive"))
      (node (ref "DAC") (pin "4") (pinfunction "AVDD_4") (pintype "power_in"))
      (node (ref "IC2") (pin "8") (pinfunction "V+_8") (pintype "power_in"))
      (node (ref "IC4") (pin "8") (pinfunction "V+_8") (pintype "power_in"))
      (node (ref "U2") (pin "5") (pinfunction "OUT_5") (pintype "bidirectional"))
    )
    (net (code "2") (name "+3V3D") (class "Default")
      (node (ref "C1") (pin "1") (pinfunction "1_1") (pintype "passive"))
      (node (ref "C8") (pin "1") (pinfunction "1_1") (pintype "passive"))
      (node (ref "DAC") (pin "12") (pinfunction "IOVDD_12") (pintype "power_in"))
      (node (ref "JP1") (pin "2") (pinfunction "2_2") (pintype "passive"))
      (node (ref "R1") (pin "2") (pinfunction "2_2") (pintype "passive"))
      (node (ref "R43") (pin "2") (pinfunction "2_2") (pintype "passive"))
      (node (ref "TEENSY3.2") (pin "3.3V") (pinfunction "3.3V_3.3V") (pintype "power_in"))
      (node (ref "U1") (pin "3") (pinfunction "VCC_3") (pintype "power_in"))
    )
    (net (code "3") (name "+5V") (class "Default")
      (node (ref "C4") (pin "1") (pinfunction "1_1") (pintype "passive"))
      (node (ref "C5") (pin "1") (pinfunction "1_1") (pintype "passive"))
      (node (ref "C9") (pin "1") (pinfunction "1_1") (pintype "passive"))
      (node (ref "L1") (pin "2") (pinfunction "2_2") (pintype "passive"))
      (node (ref "TEENSY3.2") (pin "VIN") (pinfunction "VIN_VIN") (pintype "power_in"))
      (node (ref "U2") (pin "1") (pinfunction "IN_1") (pintype "bidirectional"))
      (node (ref "U2") (pin "3") (pinfunction "EN_3") (pintype "bidirectional"))
    )
    (net (code "4") (name "+12V") (class "Default")
      (node (ref "C29") (pin "1") (pinfunction "1_1") (pintype "passive"))
      (node (ref "C7") (pin "1") (pinfunction "1_1") (pintype "passive"))
      (node (ref "C74") (pin "+") (pinfunction "+_+") (pintype "passive"))
      (node (ref "C76") (pin "1") (pinfunction "1_1") (pintype "passive"))
      (node (ref "C78") (pin "1") (pinfunction "1_1") (pintype "passive"))
      (node (ref "D9") (pin "C") (pinfunction "C_C") (pintype "passive"))
      (node (ref "IC1") (pin "2") (pinfunction "IN_2") (pintype "input"))
      (node (ref "IC7") (pin "4") (pinfunction "V+_4") (pintype "power_in"))
    )
    (net (code "5") (name "-12V") (class "Default")
      (node (ref "C23") (pin "1") (pinfunction "1_1") (pintype "passive"))
      (node (ref "C36") (pin "2") (pinfunction "2_2") (pintype "passive"))
      (node (ref "C75") (pin "-") (pinfunction "-_-") (pintype "passive"))
      (node (ref "C77") (pin "2") (pinfunction "2_2") (pintype "passive"))
      (node (ref "C79") (pin "2") (pinfunction "2_2") (pintype "passive"))
      (node (ref "D11") (pin "A") (pinfunction "A_A") (pintype "passive"))
      (node (ref "IC7") (pin "11") (pinfunction "V-_11") (pintype "power_in"))
      (node (ref "R32") (pin "2") (pinfunction "2_2") (pintype "passive"))
    )
    (net (code "6") (name "CS_DAC") (class "Default")
      (node (ref "DAC") (pin "9") (pinfunction "~{SYNC}_9") (pintype "input"))
      (node (ref "TEENSY3.2") (pin "10") (pinfunction "10/TX2/PWM_10") (pintype "bidirectional"))
    )
    (net (code "7") (name "CS_OLED") (class "Default")
      (node (ref "JP1") (pin "7") (pinfunction "7_7") (pintype "passive"))
      (node (ref "R1") (pin "1") (pinfunction "1_1") (pintype "passive"))
      (node (ref "TEENSY3.2") (pin "8") (pinfunction "8/TX3_8") (pintype "bidirectional"))
    )
    (net (code "8") (name "CV1") (class "Default")
      (node (ref "R17") (pin "2") (pinfunction "2_2") (pintype "passive"))
      (node (ref "TEENSY3.2") (pin "19/A5") (pinfunction "19/A5/T/SCL0_19/A5") (pintype "bidirectional"))
    )
    (net (code "9") (name "CV2") (class "Default")
      (node (ref "R21") (pin "2") (pinfunction "2_2") (pintype "passive"))
      (node (ref "TEENSY3.2") (pin "18/A4") (pinfunction "18/A4/T/SDA0_18/A4") (pintype "bidirectional"))
    )
    (net (code "10") (name "CV3") (class "Default")
      (node (ref "R25") (pin "2") (pinfunction "2_2") (pintype "passive"))
      (node (ref "TEENSY3.2") (pin "20/A6") (pinfunction "20/A6/PWM_20/A6") (pintype "bidirectional"))
    )
    (net (code "11") (name "CV4") (class "Default")
      (node (ref "R29") (pin "2") (pinfunction "2_2") (pintype "passive"))
      (node (ref "TEENSY3.2") (pin "17/A3") (pinfunction "17/A3/T_17/A3") (pintype "bidirectional"))
    )
    (net (code "12") (name "CV_A") (class "Default")
      (node (ref "DAC") (pin "1") (pinfunction "VOUTA_1") (pintype "output"))
      (node (ref "R10") (pin "1") (pinfunction "1_1") (pintype "passive"))
    )
    (net (code "13") (name "CV_B") (class "Default")
      (node (ref "DAC") (pin "2") (pinfunction "VOUTB_2") (pintype "output"))
      (node (ref "R13") (pin "1") (pinfunction "1_1") (pintype "passive"))
    )
    (net (code "14") (name "CV_C") (class "Default")
      (node (ref "DAC") (pin "7") (pinfunction "VOUTC_7") (pintype "output"))
      (node (ref "R4") (pin "1") (pinfunction "1_1") (pintype "passive"))
    )
    (net (code "15") (name "CV_D") (class "Default")
      (node (ref "DAC") (pin "8") (pinfunction "VOUTD_8") (pintype "output"))
      (node (ref "R7") (pin "1") (pinfunction "1_1") (pintype "passive"))
    )
    (net (code "16") (name "DC") (class "Default")
      (node (ref "JP1") (pin "6") (pinfunction "6_6") (pintype "passive"))
      (node (ref "TEENSY3.2") (pin "6") (pinfunction "6/PWM_6") (pintype "bidirectional"))
    )
    (net (code "17") (name "DOUT") (class "Default")
      (node (ref "DAC") (pin "11") (pinfunction "DIN_11") (pintype "input"))
      (node (ref "JP1") (pin "4") (pinfunction "4_4") (pintype "passive"))
      (node (ref "TEENSY3.2") (pin "11") (pinfunction "11/MOSI_11") (pintype "bidirectional"))
    )
    (net (code "18") (name "ENC_L1") (class "Default")
      (node (ref "SW2") (pin "B") (pinfunction "B_B") (pintype "passive"))
      (node (ref "TEENSY3.2") (pin "22/A8") (pinfunction "22/A8/T/PWM_22/A8") (pintype "bidirectional"))
    )
    (net (code "19") (name "ENC_L2") (class "Default")
      (node (ref "SW2") (pin "A") (pinfunction "A_A") (pintype "passive"))
      (node (ref "TEENSY3.2") (pin "21/A7") (pinfunction "21/A7/PWM_21/A7") (pintype "bidirectional"))
    )
    (net (code "20") (name "ENC_R1") (class "Default")
      (node (ref "SW1") (pin "B") (pinfunction "B_B") (pintype "passive"))
      (node (ref "TEENSY3.2") (pin "15/A1") (pinfunction "15/A1/T_15/A1") (pintype "bidirectional"))
    )
    (net (code "21") (name "ENC_R2") (class "Default")
      (node (ref "SW1") (pin "A") (pinfunction "A_A") (pintype "passive"))
      (node (ref "TEENSY3.2") (pin "16/A2") (pinfunction "16/A2/T_16/A2") (pintype "bidirectional"))
    )
    (net (code "22") (name "GND") (class "Default")
      (node (ref "C1") (pin "2") (pinfunction "2_2") (pintype "passive"))
      (node (ref "C14") (pin "2") (pinfunction "2_2") (pintype "passive"))
      (node (ref "C15") (pin "2") (pinfunction "2_2") (pintype "passive"))
      (node (ref "C16") (pin "2") (pinfunction "2_2") (pintype "passive"))
      (node (ref "C17") (pin "2") (pinfunction "2_2") (pintype "passive"))
      (node (ref "C2") (pin "2") (pinfunction "2_2") (pintype "passive"))
      (node (ref "C22") (pin "2") (pinfunction "2_2") (pintype "passive"))
      (node (ref "C23") (pin "2") (pinfunction "2_2") (pintype "passive"))
      (node (ref "C24") (pin "2") (pinfunction "2_2") (pintype "passive"))
      (node (ref "C25") (pin "1") (pinfunction "1_1") (pintype "passive"))
      (node (ref "C28") (pin "2") (pinfunction "2_2") (pintype "passive"))
      (node (ref "C29") (pin "2") (pinfunction "2_2") (pintype "passive"))
      (node (ref "C3") (pin "2") (pinfunction "2_2") (pintype "passive"))
      (node (ref "C35") (pin "2") (pinfunction "2_2") (pintype "passive"))
      (node (ref "C36") (pin "1") (pinfunction "1_1") (pintype "passive"))
      (node (ref "C37") (pin "2") (pinfunction "2_2") (pintype "passive"))
      (node (ref "C4") (pin "2") (pinfunction "2_2") (pintype "passive"))
      (node (ref "C5") (pin "2") (pinfunction "2_2") (pintype "passive"))
      (node (ref "C6") (pin "2") (pinfunction "2_2") (pintype "passive"))
      (node (ref "C7") (pin "2") (pinfunction "2_2") (pintype "passive"))
      (node (ref "C74") (pin "-") (pinfunction "-_-") (pintype "passive"))
      (node (ref "C75") (pin "+") (pinfunction "+_+") (pintype "passive"))
      (node (ref "C76") (pin "2") (pinfunction "2_2") (pintype "passive"))
      (node (ref "C77") (pin "1") (pinfunction "1_1") (pintype "passive"))
      (node (ref "C78") (pin "2") (pinfunction "2_2") (pintype "passive"))
      (node (ref "C79") (pin "1") (pinfunction "1_1") (pintype "passive"))
      (node (ref "C8") (pin "2") (pinfunction "2_2") (pintype "passive"))
      (node (ref "C9") (pin "2") (pinfunction "2_2") (pintype "passive"))
      (node (ref "D1") (pin "A") (pinfunction "A_A") (pintype "passive"))
      (node (ref "D2") (pin "A") (pinfunction "A_A") (pintype "passive"))
      (node (ref "D3") (pin "A") (pinfunction "A_A") (pintype "passive"))
      (node (ref "D4") (pin "A") (pinfunction "A_A") (pintype "passive"))
      (node (ref "DAC") (pin "14") (pinfunction "RSTSEL_14") (pintype "input"))
      (node (ref "DAC") (pin "15") (pinfunction "~{ENABLE}_15") (pintype "input"))
      (node (ref "DAC") (pin "16") (pinfunction "LDAC_16") (pintype "input"))
      (node (ref "DAC") (pin "5") (pinfunction "VREFL_5") (pintype "input"))
      (node (ref "DAC") (pin "6") (pinfunction "GND_6") (pintype "passive"))
      (node (ref "DOWNSW") (pin "1") (pinfunction "1_1") (pintype "passive"))
      (node (ref "DOWNSW") (pin "2") (pinfunction "2_2") (pintype "passive"))
      (node (ref "IC1") (pin "1") (pinfunction "GND_1") (pintype "input"))
      (node (ref "IC2") (pin "3") (pinfunction "+IN_3") (pintype "input"))
      (node (ref "IC2") (pin "4") (pinfunction "V-_4") (pintype "power_in"))
      (node (ref "IC2") (pin "5") (pinfunction "+IN_5") (pintype "input"))
      (node (ref "IC4") (pin "3") (pinfunction "+IN_3") (pintype "input"))
      (node (ref "IC4") (pin "4") (pinfunction "V-_4") (pintype "power_in"))
      (node (ref "IC4") (pin "5") (pinfunction "+IN_5") (pintype "input"))
      (node (ref "IC5") (pin "1") (pinfunction "C_1") (pintype "passive"))
      (node (ref "J2") (pin "2") (pinfunction "2_2") (pintype "passive"))
      (node (ref "J2") (pin "3") (pinfunction "3_3") (pintype "passive"))
      (node (ref "J3") (pin "2") (pinfunction "3_2") (pintype "bidirectional"))
      (node (ref "J3") (pin "3") (pinfunction "2_3") (pintype "bidirectional"))
      (node (ref "JP1") (pin "1") (pinfunction "1_1") (pintype "passive"))
      (node (ref "R15") (pin "1") (pinfunction "1_1") (pintype "passive"))
      (node (ref "R34") (pin "1") (pinfunction "1_1") (pintype "passive"))
      (node (ref "R36") (pin "1") (pinfunction "1_1") (pintype "passive"))
      (node (ref "R38") (pin "1") (pinfunction "1_1") (pintype "passive"))
      (node (ref "R40") (pin "1") (pinfunction "1_1") (pintype "passive"))
      (node (ref "SW1") (pin "C") (pinfunction "C_C") (pintype "passive"))
      (node (ref "SW1") (pin "D") (pinfunction "1_D") (pintype "passive"))
      (node (ref "SW2") (pin "C") (pinfunction "C_C") (pintype "passive"))
      (node (ref "SW2") (pin "D") (pinfunction "1_D") (pintype "passive"))
      (node (ref "T1") (pin "E") (pinfunction "E_E") (pintype "passive"))
      (node (ref "T2") (pin "E") (pinfunction "E_E") (pintype "passive"))
      (node (ref "T3") (pin "E") (pinfunction "E_E") (pintype "passive"))
      (node (ref "T4") (pin "E") (pinfunction "E_E") (pintype "passive"))
      (node (ref "TEENSY3.2") (pin "AGND") (pinfunction "AGND_AGND") (pintype "power_in"))
      (node (ref "TEENSY3.2") (pin "GND") (pinfunction "GND_GND") (pintype "power_in"))
      (node (ref "U1") (pin "1") (pinfunction "GND_1") (pintype "passive"))
      (node (ref "U2") (pin "2") (pinfunction "GND_2") (pintype "bidirectional"))
      (node (ref "UPSW") (pin "1") (pinfunction "1_1") (pintype "passive"))
      (node (ref "UPSW") (pin "2") (pinfunction "2_2") (pintype "passive"))
    )
    (net (code "23") (name "Net-(A-1)") (class "Default")
      (node (ref "A") (pin "P$1") (pinfunction "1_P$1") (pintype "passive"))
      (node (ref "CV_A") (pin "1") (pinfunction "1_1") (pintype "passive"))
      (node (ref "R8") (pin "2") (pinfunction "2_2") (pintype "passive"))
      (node (ref "R9") (pin "2") (pinfunction "2_2") (pintype "passive"))
    )
    (net (code "24") (name "Net-(B-1)") (class "Default")
      (node (ref "B") (pin "P$1") (pinfunction "1_P$1") (pintype "passive"))
      (node (ref "CV_B") (pin "1") (pinfunction "1_1") (pintype "passive"))
      (node (ref "R11") (pin "2") (pinfunction "2_2") (pintype "passive"))
      (node (ref "R12") (pin "2") (pinfunction "2_2") (pintype "passive"))
    )
    (net (code "25") (name "Net-(C-1)") (class "Default")
      (node (ref "C") (pin "P$1") (pinfunction "1_P$1") (pintype "passive"))
      (node (ref "CV_C") (pin "1") (pinfunction "1_1") (pintype "passive"))
      (node (ref "R2") (pin "2") (pinfunction "2_2") (pintype "passive"))
      (node (ref "R3") (pin "2") (pinfunction "2_2") (pintype "passive"))
    )
    (net (code "26") (name "Net-(CV1-1)") (class "Default")
      (node (ref "CV1") (pin "P$1") (pinfunction "1_P$1") (pintype "passive"))
      (node (ref "CVIN1") (pin "1") (pinfunction "1_1") (pintype "passive"))
      (node (ref "R18") (pin "1") (pinfunction "1_1") (pintype "passive"))
    )
    (net (code "27") (name "Net-(CV2-1)") (class "Default")
      (node (ref "CV2") (pin "P$1") (pinfunction "1_P$1") (pintype "passive"))
      (node (ref "CVIN2") (pin "1") (pinfunction "1_1") (pintype "passive"))
      (node (ref "R22") (pin "1") (pinfunction "1_1") (pintype "passive"))
    )
    (net (code "28") (name "Net-(CV3-1)") (class "Default")
      (node (ref "CV3") (pin "P$1") (pinfunction "1_P$1") (pintype "passive"))
      (node (ref "CVIN3") (pin "1") (pinfunction "1_1") (pintype "passive"))
      (node (ref "R26") (pin "1") (pinfunction "1_1") (pintype "passive"))
    )
    (net (code "29") (name "Net-(CV4-1)") (class "Default")
      (node (ref "CV4") (pin "P$1") (pinfunction "1_P$1") (pintype "passive"))
      (node (ref "CVIN4") (pin "1") (pinfunction "1_1") (pintype "passive"))
      (node (ref "R30") (pin "1") (pinfunction "1_1") (pintype "passive"))
    )
    (net (code "30") (name "Net-(D-1)") (class "Default")
      (node (ref "CV_D") (pin "1") (pinfunction "1_1") (pintype "passive"))
      (node (ref "D") (pin "P$1") (pinfunction "1_P$1") (pintype "passive"))
      (node (ref "R5") (pin "2") (pinfunction "2_2") (pintype "passive"))
      (node (ref "R6") (pin "2") (pinfunction "2_2") (pintype "passive"))
    )
    (net (code "31") (name "Net-(D1-PadC)") (class "Default")
      (node (ref "D1") (pin "C") (pinfunction "C_C") (pintype "passive"))
      (node (ref "R39") (pin "2") (pinfunction "2_2") (pintype "passive"))
      (node (ref "R40") (pin "2") (pinfunction "2_2") (pintype "passive"))
      (node (ref "T4") (pin "B") (pinfunction "B_B") (pintype "passive"))
    )
    (net (code "32") (name "Net-(D2-PadC)") (class "Default")
      (node (ref "D2") (pin "C") (pinfunction "C_C") (pintype "passive"))
      (node (ref "R37") (pin "2") (pinfunction "2_2") (pintype "passive"))
      (node (ref "R38") (pin "2") (pinfunction "2_2") (pintype "passive"))
      (node (ref "T3") (pin "B") (pinfunction "B_B") (pintype "passive"))
    )
    (net (code "33") (name "Net-(D3-PadC)") (class "Default")
      (node (ref "D3") (pin "C") (pinfunction "C_C") (pintype "passive"))
      (node (ref "R35") (pin "2") (pinfunction "2_2") (pintype "passive"))
      (node (ref "R36") (pin "2") (pinfunction "2_2") (pintype "passive"))
      (node (ref "T2") (pin "B") (pinfunction "B_B") (pintype "passive"))
    )
    (net (code "34") (name "Net-(D4-PadC)") (class "Default")
      (node (ref "D4") (pin "C") (pinfunction "C_C") (pintype "passive"))
      (node (ref "R33") (pin "2") (pinfunction "2_2") (pintype "passive"))
      (node (ref "R34") (pin "2") (pinfunction "2_2") (pintype "passive"))
      (node (ref "T1") (pin "B") (pinfunction "B_B") (pintype "passive"))
    )
    (net (code "35") (name "Net-(DOWNSW-Pad3)") (class "Default")
      (node (ref "DOWNSW") (pin "3") (pinfunction "3_3") (pintype "passive"))
      (node (ref "DOWNSW") (pin "4") (pinfunction "4_4") (pintype "passive"))
      (node (ref "R42") (pin "1") (pinfunction "1_1") (pintype "passive"))
    )
    (net (code "36") (name "Net-(IC1-OUT)") (class "Default")
      (node (ref "C6") (pin "1") (pinfunction "1_1") (pintype "passive"))
      (node (ref "IC1") (pin "3") (pinfunction "OUT_3") (pintype "passive"))
      (node (ref "L1") (pin "1") (pinfunction "1_1") (pintype "passive"))
    )
    (net (code "37") (name "Net-(IC2A--IN)") (class "Default")
      (node (ref "C18") (pin "1") (pinfunction "1_1") (pintype "passive"))
      (node (ref "IC2") (pin "2") (pinfunction "-IN_2") (pintype "input"))
      (node (ref "R16") (pin "1") (pinfunction "1_1") (pintype "passive"))
      (node (ref "R18") (pin "2") (pinfunction "2_2") (pintype "passive"))
      (node (ref "R19") (pin "2") (pinfunction "2_2") (pintype "passive"))
    )
    (net (code "38") (name "Net-(IC2A-OUT)") (class "Default")
      (node (ref "C18") (pin "2") (pinfunction "2_2") (pintype "passive"))
      (node (ref "IC2") (pin "1") (pinfunction "OUT_1") (pintype "output"))
      (node (ref "R16") (pin "2") (pinfunction "2_2") (pintype "passive"))
      (node (ref "R17") (pin "1") (pinfunction "1_1") (pintype "passive"))
    )
    (net (code "39") (name "Net-(IC2B--IN)") (class "Default")
      (node (ref "C19") (pin "1") (pinfunction "1_1") (pintype "passive"))
      (node (ref "IC2") (pin "6") (pinfunction "-IN_6") (pintype "input"))
      (node (ref "R20") (pin "1") (pinfunction "1_1") (pintype "passive"))
      (node (ref "R22") (pin "2") (pinfunction "2_2") (pintype "passive"))
      (node (ref "R23") (pin "2") (pinfunction "2_2") (pintype "passive"))
    )
    (net (code "40") (name "Net-(IC2B-OUT)") (class "Default")
      (node (ref "C19") (pin "2") (pinfunction "2_2") (pintype "passive"))
      (node (ref "IC2") (pin "7") (pinfunction "OUT_7") (pintype "output"))
      (node (ref "R20") (pin "2") (pinfunction "2_2") (pintype "passive"))
      (node (ref "R21") (pin "1") (pinfunction "1_1") (pintype "passive"))
    )
    (net (code "41") (name "Net-(IC4A--IN)") (class "Default")
      (node (ref "C21") (pin "1") (pinfunction "1_1") (pintype "passive"))
      (node (ref "IC4") (pin "2") (pinfunction "-IN_2") (pintype "input"))
      (node (ref "R28") (pin "1") (pinfunction "1_1") (pintype "passive"))
      (node (ref "R30") (pin "2") (pinfunction "2_2") (pintype "passive"))
      (node (ref "R31") (pin "2") (pinfunction "2_2") (pintype "passive"))
    )
    (net (code "42") (name "Net-(IC4A-OUT)") (class "Default")
      (node (ref "C21") (pin "2") (pinfunction "2_2") (pintype "passive"))
      (node (ref "IC4") (pin "1") (pinfunction "OUT_1") (pintype "output"))
      (node (ref "R28") (pin "2") (pinfunction "2_2") (pintype "passive"))
      (node (ref "R29") (pin "1") (pinfunction "1_1") (pintype "passive"))
    )
    (net (code "43") (name "Net-(IC4B--IN)") (class "Default")
      (node (ref "C20") (pin "1") (pinfunction "1_1") (pintype "passive"))
      (node (ref "IC4") (pin "6") (pinfunction "-IN_6") (pintype "input"))
      (node (ref "R24") (pin "1") (pinfunction "1_1") (pintype "passive"))
      (node (ref "R26") (pin "2") (pinfunction "2_2") (pintype "passive"))
      (node (ref "R27") (pin "2") (pinfunction "2_2") (pintype "passive"))
    )
    (net (code "44") (name "Net-(IC4B-OUT)") (class "Default")
      (node (ref "C20") (pin "2") (pinfunction "2_2") (pintype "passive"))
      (node (ref "IC4") (pin "7") (pinfunction "OUT_7") (pintype "output"))
      (node (ref "R24") (pin "2") (pinfunction "2_2") (pintype "passive"))
      (node (ref "R25") (pin "1") (pinfunction "1_1") (pintype "passive"))
    )
    (net (code "45") (name "Net-(IC7A--IN)") (class "Default")
      (node (ref "C12") (pin "1") (pinfunction "1_1") (pintype "passive"))
      (node (ref "IC7") (pin "2") (pinfunction "-IN_2") (pintype "input"))
      (node (ref "R10") (pin "2") (pinfunction "2_2") (pintype "passive"))
      (node (ref "R9") (pin "1") (pinfunction "1_1") (pintype "passive"))
    )
    (net (code "46") (name "Net-(IC7A-OUT)") (class "Default")
      (node (ref "C12") (pin "2") (pinfunction "2_2") (pintype "passive"))
      (node (ref "IC7") (pin "1") (pinfunction "OUT_1") (pintype "output"))
      (node (ref "R8") (pin "1") (pinfunction "1_1") (pintype "passive"))
    )
    (net (code "47") (name "Net-(IC7B--IN)") (class "Default")
      (node (ref "C10") (pin "1") (pinfunction "1_1") (pintype "passive"))
      (node (ref "IC7") (pin "6") (pinfunction "-IN_6") (pintype "input"))
      (node (ref "R3") (pin "1") (pinfunction "1_1") (pintype "passive"))
      (node (ref "R4") (pin "2") (pinfunction "2_2") (pintype "passive"))
    )
    (net (code "48") (name "Net-(IC7B-OUT)") (class "Default")
      (node (ref "C10") (pin "2") (pinfunction "2_2") (pintype "passive"))
      (node (ref "IC7") (pin "7") (pinfunction "OUT_7") (pintype "output"))
      (node (ref "R2") (pin "1") (pinfunction "1_1") (pintype "passive"))
    )
    (net (code "49") (name "Net-(IC7C--IN)") (class "Default")
      (node (ref "C11") (pin "1") (pinfunction "1_1") (pintype "passive"))
      (node (ref "IC7") (pin "9") (pinfunction "-IN_9") (pintype "input"))
      (node (ref "R6") (pin "1") (pinfunction "1_1") (pintype "passive"))
      (node (ref "R7") (pin "2") (pinfunction "2_2") (pintype "passive"))
    )
    (net (code "50") (name "Net-(IC7C-OUT)") (class "Default")
      (node (ref "C11") (pin "2") (pinfunction "2_2") (pintype "passive"))
      (node (ref "IC7") (pin "8") (pinfunction "OUT_8") (pintype "output"))
      (node (ref "R5") (pin "1") (pinfunction "1_1") (pintype "passive"))
    )
    (net (code "51") (name "Net-(IC7D--IN)") (class "Default")
      (node (ref "C13") (pin "1") (pinfunction "1_1") (pintype "passive"))
      (node (ref "IC7") (pin "13") (pinfunction "-IN_13") (pintype "input"))
      (node (ref "R12") (pin "1") (pinfunction "1_1") (pintype "passive"))
      (node (ref "R13") (pin "2") (pinfunction "2_2") (pintype "passive"))
    )
    (net (code "52") (name "Net-(IC7D-OUT)") (class "Default")
      (node (ref "C13") (pin "2") (pinfunction "2_2") (pintype "passive"))
      (node (ref "IC7") (pin "14") (pinfunction "OUT_14") (pintype "output"))
      (node (ref "R11") (pin "1") (pinfunction "1_1") (pintype "passive"))
    )
    (net (code "53") (name "Net-(J3-1)") (class "Default")
      (node (ref "D11") (pin "C") (pinfunction "C_C") (pintype "passive"))
      (node (ref "J2") (pin "4") (pinfunction "4_4") (pintype "passive"))
      (node (ref "J3") (pin "4") (pinfunction "1_4") (pintype "bidirectional"))
    )
    (net (code "54") (name "Net-(J3-4)") (class "Default")
      (node (ref "D9") (pin "A") (pinfunction "A_A") (pintype "passive"))
      (node (ref "J2") (pin "1") (pinfunction "1_1") (pintype "passive"))
      (node (ref "J3") (pin "1") (pinfunction "4_1") (pintype "bidirectional"))
    )
    (net (code "55") (name "Net-(R41-Pad1)") (class "Default")
      (node (ref "R41") (pin "1") (pinfunction "1_1") (pintype "passive"))
      (node (ref "UPSW") (pin "3") (pinfunction "3_3") (pintype "passive"))
      (node (ref "UPSW") (pin "4") (pinfunction "4_4") (pintype "passive"))
    )
    (net (code "56") (name "Net-(TRIG1-1)") (class "Default")
      (node (ref "R33") (pin "1") (pinfunction "1_1") (pintype "passive"))
      (node (ref "TR1") (pin "1") (pinfunction "1_1") (pintype "passive"))
      (node (ref "TRIG1") (pin "P$1") (pinfunction "1_P$1") (pintype "passive"))
    )
    (net (code "57") (name "Net-(TRIG2-1)") (class "Default")
      (node (ref "R35") (pin "1") (pinfunction "1_1") (pintype "passive"))
      (node (ref "TR2") (pin "1") (pinfunction "1_1") (pintype "passive"))
      (node (ref "TRIG2") (pin "P$1") (pinfunction "1_P$1") (pintype "passive"))
    )
    (net (code "58") (name "Net-(TRIG3-1)") (class "Default")
      (node (ref "R37") (pin "1") (pinfunction "1_1") (pintype "passive"))
      (node (ref "TR3") (pin "1") (pinfunction "1_1") (pintype "passive"))
      (node (ref "TRIG3") (pin "P$1") (pinfunction "1_P$1") (pintype "passive"))
    )
    (net (code "59") (name "Net-(TRIG4-1)") (class "Default")
      (node (ref "R39") (pin "1") (pinfunction "1_1") (pintype "passive"))
      (node (ref "TR4") (pin "1") (pinfunction "1_1") (pintype "passive"))
      (node (ref "TRIG4") (pin "P$1") (pinfunction "1_P$1") (pintype "passive"))
    )
    (net (code "60") (name "OFFSET") (class "Default")
      (node (ref "C22") (pin "1") (pinfunction "1_1") (pintype "passive"))
      (node (ref "IC5") (pin "2") (pinfunction "A_2") (pintype "passive"))
      (node (ref "R19") (pin "1") (pinfunction "1_1") (pintype "passive"))
      (node (ref "R23") (pin "1") (pinfunction "1_1") (pintype "passive"))
      (node (ref "R27") (pin "1") (pinfunction "1_1") (pintype "passive"))
      (node (ref "R31") (pin "1") (pinfunction "1_1") (pintype "passive"))
      (node (ref "R32") (pin "1") (pinfunction "1_1") (pintype "passive"))
    )
    (net (code "61") (name "POGO") (class "Default")
      (node (ref "R43") (pin "1") (pinfunction "1_1") (pintype "passive"))
      (node (ref "U1") (pin "2") (pinfunction "~{RESET}_2") (pintype "passive"))
    )
    (net (code "62") (name "RST") (class "Default")
      (node (ref "JP1") (pin "5") (pinfunction "5_5") (pintype "passive"))
      (node (ref "TEENSY3.2") (pin "7") (pinfunction "7/RX3_7") (pintype "bidirectional"))
    )
    (net (code "63") (name "RST_DAC") (class "Default")
      (node (ref "DAC") (pin "13") (pinfunction "~{RST}_13") (pintype "input"))
      (node (ref "TEENSY3.2") (pin "9") (pinfunction "9/RX2/PWM_9") (pintype "bidirectional"))
    )
    (net (code "64") (name "SCK") (class "Default")
      (node (ref "DAC") (pin "10") (pinfunction "SCLK_10") (pintype "input"))
      (node (ref "JP1") (pin "3") (pinfunction "3_3") (pintype "passive"))
      (node (ref "TEENSY3.2") (pin "13") (pinfunction "13/SCK/LED_13") (pintype "bidirectional"))
    )
    (net (code "65") (name "SW_B") (class "Default")
      (node (ref "C24") (pin "1") (pinfunction "1_1") (pintype "passive"))
      (node (ref "R42") (pin "2") (pinfunction "2_2") (pintype "passive"))
      (node (ref "TEENSY3.2") (pin "4") (pinfunction "4/CAN-RX/PWM_4") (pintype "bidirectional"))
    )
    (net (code "66") (name "SW_L") (class "Default")
      (node (ref "C17") (pin "1") (pinfunction "1_1") (pintype "passive"))
      (node (ref "SW2") (pin "E") (pinfunction "2_E") (pintype "passive"))
      (node (ref "TEENSY3.2") (pin "23/A9") (pinfunction "23/A9/T/PWM_23/A9") (pintype "bidirectional"))
    )
    (net (code "67") (name "SW_R") (class "Default")
      (node (ref "SW1") (pin "E") (pinfunction "2_E") (pintype "passive"))
      (node (ref "TEENSY3.2") (pin "14/A0") (pinfunction "14/A1_14/A0") (pintype "bidirectional"))
    )
    (net (code "68") (name "SW_T") (class "Default")
      (node (ref "C25") (pin "2") (pinfunction "2_2") (pintype "passive"))
      (node (ref "R41") (pin "2") (pinfunction "2_2") (pintype "passive"))
      (node (ref "TEENSY3.2") (pin "5") (pinfunction "5/PWM_5") (pintype "bidirectional"))
    )
    (net (code "69") (name "TR1") (class "Default")
      (node (ref "T1") (pin "C") (pinfunction "C_C") (pintype "passive"))
      (node (ref "TEENSY3.2") (pin "0") (pinfunction "0/RX1/T_0") (pintype "bidirectional"))
    )
    (net (code "70") (name "TR2") (class "Default")
      (node (ref "T2") (pin "C") (pinfunction "C_C") (pintype "passive"))
      (node (ref "TEENSY3.2") (pin "1") (pinfunction "1/TX1/T_1") (pintype "bidirectional"))
    )
    (net (code "71") (name "TR3") (class "Default")
      (node (ref "T3") (pin "C") (pinfunction "C_C") (pintype "passive"))
      (node (ref "TEENSY3.2") (pin "2") (pinfunction "2_2") (pintype "bidirectional"))
    )
    (net (code "72") (name "TR4") (class "Default")
      (node (ref "T4") (pin "C") (pinfunction "C_C") (pintype "passive"))
      (node (ref "TEENSY3.2") (pin "3") (pinfunction "3/CAN-TX/PWM_3") (pintype "bidirectional"))
    )
    (net (code "73") (name "UNUSED") (class "Default")
      (node (ref "TEENSY3.2") (pin "12") (pinfunction "12/MISO_12") (pintype "bidirectional"))
    )
    (net (code "74") (name "VREF_2V5") (class "Default")
      (node (ref "C14") (pin "1") (pinfunction "1_1") (pintype "passive"))
      (node (ref "C15") (pin "1") (pinfunction "1_1") (pintype "passive"))
      (node (ref "DAC") (pin "3") (pinfunction "VREFH/VREFOUT_3") (pintype "bidirectional"))
      (node (ref "R14") (pin "2") (pinfunction "2_2") (pintype "passive"))
    )
    (net (code "75") (name "V_BIAS") (class "Default")
      (node (ref "C16") (pin "1") (pinfunction "1_1") (pintype "passive"))
      (node (ref "IC7") (pin "10") (pinfunction "+IN_10") (pintype "input"))
      (node (ref "IC7") (pin "12") (pinfunction "+IN_12") (pintype "input"))
      (node (ref "IC7") (pin "3") (pinfunction "+IN_3") (pintype "input"))
      (node (ref "IC7") (pin "5") (pinfunction "+IN_5") (pintype "input"))
      (node (ref "R14") (pin "1") (pinfunction "1_1") (pintype "passive"))
      (node (ref "R15") (pin "2") (pinfunction "2_2") (pintype "passive"))
    )
  )
)
